# 24v_reg_motor.net
KiCad netlist of a schematic drawn in EAGLE
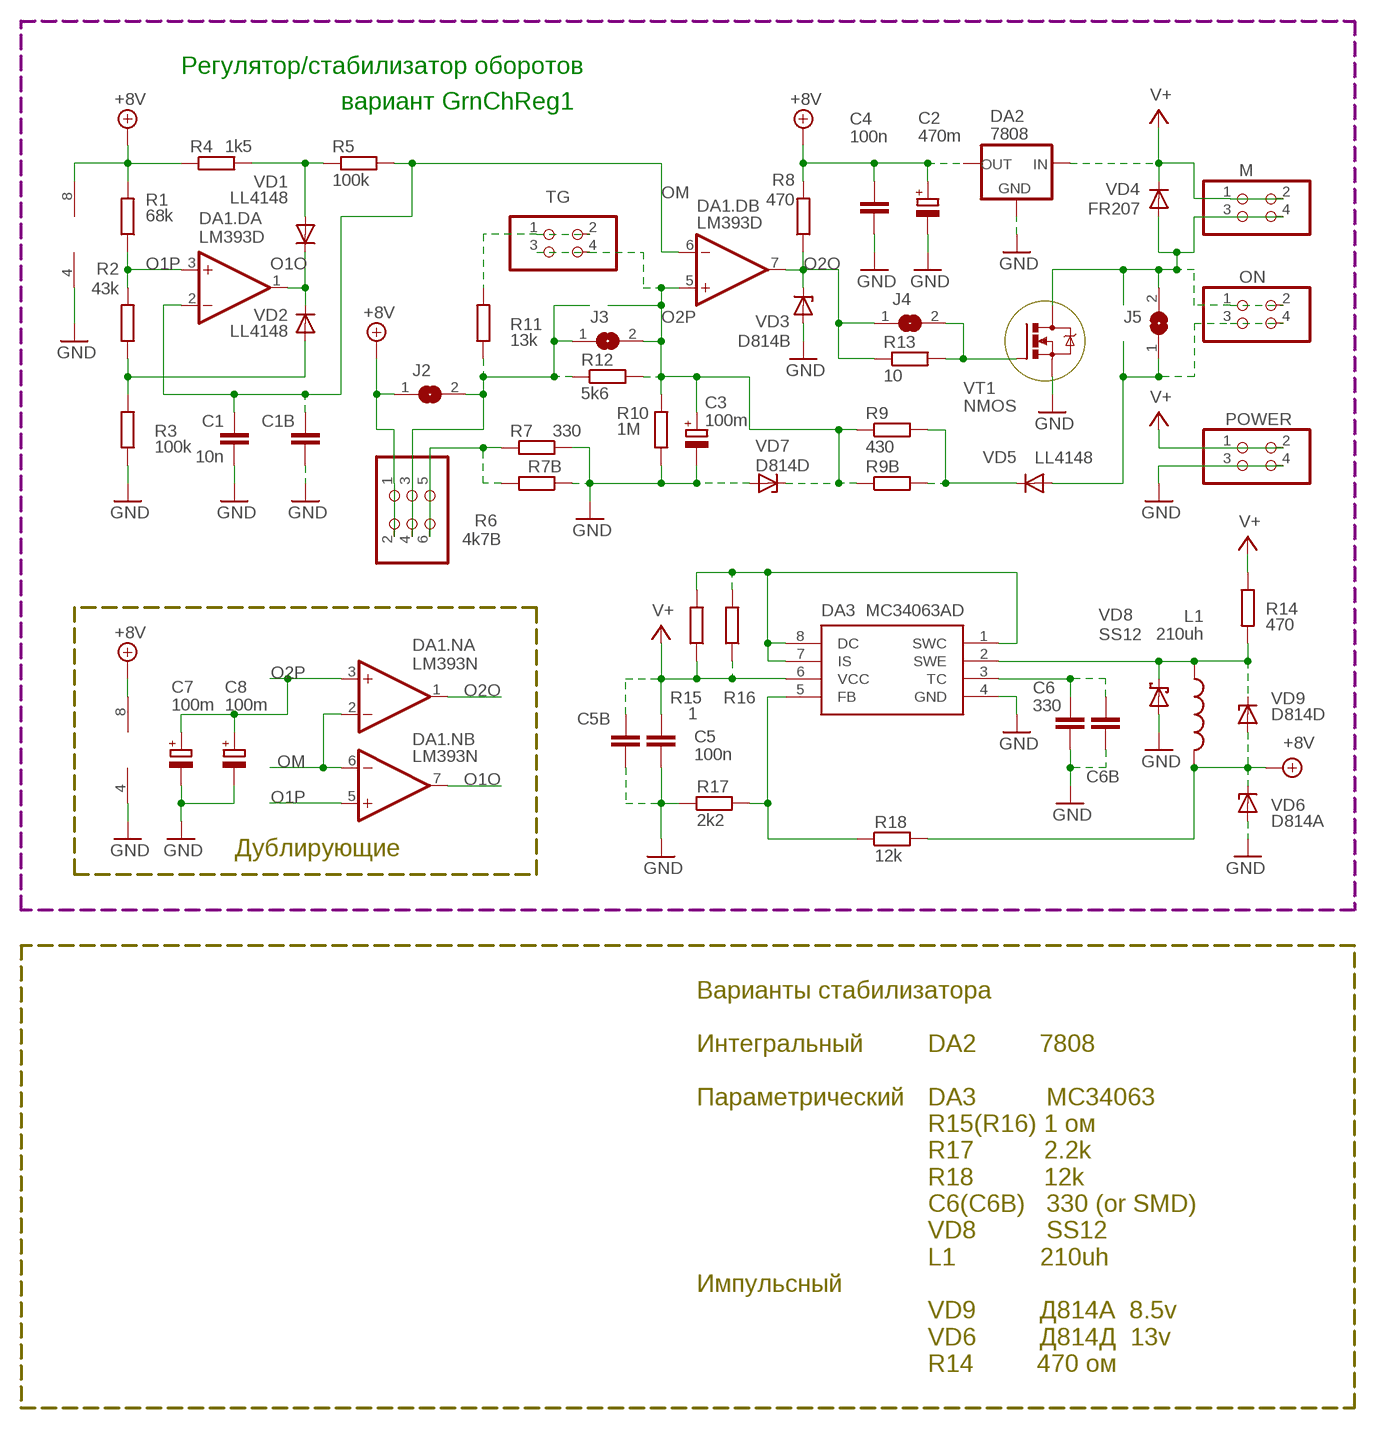
[diagram p0: schematic, sheet 1]

(export (version "E")
  (design (tool "Eeschema 10.0.6"))
  (components
    (comp (ref "C1")
      (value "10n")
      (footprint "eagle-import:C025-025X050")
      (libsource (lib "eagle-import") (part "rcl_C-EU025-025X050"))
    )
    (comp (ref "C1B")
      (value "C-EUC0805")
      (footprint "eagle-import:C0805")
      (libsource (lib "eagle-import") (part "rcl_C-EUC0805"))
    )
    (comp (ref "C2")
      (value "470m")
      (footprint "eagle-import:E5-8,5")
      (libsource (lib "eagle-import") (part "CPOL-EUE5-8.5"))
    )
    (comp (ref "C3")
      (value "100m")
      (footprint "eagle-import:E2,5-7")
      (libsource (lib "eagle-import") (part "CPOL-EUE2.5-7"))
    )
    (comp (ref "C4")
      (value "100n")
      (footprint "eagle-import:C1206K")
      (libsource (lib "eagle-import") (part "rcl_C-EUC1206K"))
    )
    (comp (ref "C5")
      (value "100n")
      (footprint "eagle-import:C025-024X044")
      (libsource (lib "eagle-import") (part "C-EU025-024X044"))
    )
    (comp (ref "C5B")
      (value "C-EUC1206")
      (footprint "eagle-import:C1206")
      (libsource (lib "eagle-import") (part "C-EUC1206"))
    )
    (comp (ref "C6")
      (value "330")
      (footprint "eagle-import:C025-025X050")
      (libsource (lib "eagle-import") (part "rcl_C-EU025-025X050"))
    )
    (comp (ref "C6B")
      (value "C-EUC0805")
      (footprint "eagle-import:C0805")
      (libsource (lib "eagle-import") (part "rcl_C-EUC0805"))
    )
    (comp (ref "C7")
      (value "100m")
      (footprint "eagle-import:E22-6")
      (libsource (lib "eagle-import") (part "CPOL-EUE22-6AXIAL"))
    )
    (comp (ref "C8")
      (value "100m")
      (footprint "eagle-import:E22-6")
      (libsource (lib "eagle-import") (part "CPOL-EUE22-6AXIAL"))
    )
    (comp (ref "DA1.D")
      (value "LM393D")
      (footprint "eagle-import:SO08")
      (libsource (lib "eagle-import") (part "LM393D"))
    )
    (comp (ref "DA1.N")
      (value "LM393N")
      (footprint "eagle-import:DIL08")
      (libsource (lib "eagle-import") (part "LM393N"))
    )
    (comp (ref "DA2")
      (value "7808")
      (footprint "eagle-import:79XXL")
      (libsource (lib "eagle-import") (part "79XXL"))
    )
    (comp (ref "DA3")
      (value "MC34063AD")
      (footprint "eagle-import:SOIC8")
      (libsource (lib "eagle-import") (part "MC34063AD"))
    )
    (comp (ref "J2") (value "SJ") (footprint "eagle-import:SJ") (libsource (lib "eagle-import") (part "SJ")))
    (comp (ref "J3") (value "SJ") (footprint "eagle-import:SJ") (libsource (lib "eagle-import") (part "SJ")))
    (comp (ref "J4") (value "SJ") (footprint "eagle-import:SJ") (libsource (lib "eagle-import") (part "SJ")))
    (comp (ref "J5") (value "SJ") (footprint "eagle-import:SJ") (libsource (lib "eagle-import") (part "SJ")))
    (comp (ref "L1")
      (value "210uh")
      (footprint "eagle-import:0207_10")
      (libsource (lib "eagle-import") (part "L-US0207/10"))
    )
    (comp (ref "M")
      (value "PINHD-2X2")
      (footprint "eagle-import:2X02")
      (libsource (lib "eagle-import") (part "PINHD-2X2"))
    )
    (comp (ref "ON")
      (value "PINHD-2X2")
      (footprint "eagle-import:2X02")
      (libsource (lib "eagle-import") (part "PINHD-2X2"))
    )
    (comp (ref "POWER")
      (value "PINHD-2X2")
      (footprint "eagle-import:2X02")
      (libsource (lib "eagle-import") (part "PINHD-2X2"))
    )
    (comp (ref "R1")
      (value "68k")
      (footprint "eagle-import:0207_10")
      (libsource (lib "eagle-import") (part "R-EU_0207/10"))
    )
    (comp (ref "R2")
      (value "43k")
      (footprint "eagle-import:M0805")
      (libsource (lib "eagle-import") (part "R-EU_M0805"))
    )
    (comp (ref "R3")
      (value "100k")
      (footprint "eagle-import:M0805")
      (libsource (lib "eagle-import") (part "R-EU_M0805"))
    )
    (comp (ref "R4")
      (value "1k5")
      (footprint "eagle-import:M0805")
      (libsource (lib "eagle-import") (part "R-EU_M0805"))
    )
    (comp (ref "R5")
      (value "100k")
      (footprint "eagle-import:M0805")
      (libsource (lib "eagle-import") (part "R-EU_M0805"))
    )
    (comp (ref "R6")
      (value "4k7B")
      (footprint "eagle-import:2X03")
      (libsource (lib "eagle-import") (part "PINHD-2X3"))
    )
    (comp (ref "R7")
      (value "330")
      (footprint "eagle-import:0309_10")
      (libsource (lib "eagle-import") (part "R-EU_0309/10"))
    )
    (comp (ref "R7B")
      (value "R-EU_M0805")
      (footprint "eagle-import:M0805")
      (libsource (lib "eagle-import") (part "R-EU_M0805"))
    )
    (comp (ref "R8")
      (value "470")
      (footprint "eagle-import:M0805")
      (libsource (lib "eagle-import") (part "R-EU_M0805"))
    )
    (comp (ref "R9")
      (value "430")
      (footprint "eagle-import:0207_10")
      (libsource (lib "eagle-import") (part "R-EU_0207/10"))
    )
    (comp (ref "R9B")
      (value "R-EU_R0805")
      (footprint "eagle-import:R0805")
      (libsource (lib "eagle-import") (part "R-EU_R0805"))
    )
    (comp (ref "R10")
      (value "1M")
      (footprint "eagle-import:M0805")
      (libsource (lib "eagle-import") (part "R-EU_M0805"))
    )
    (comp (ref "R11")
      (value "13k")
      (footprint "eagle-import:0207_10")
      (libsource (lib "eagle-import") (part "R-EU_0207/10"))
    )
    (comp (ref "R12")
      (value "5k6")
      (footprint "eagle-import:M0805")
      (libsource (lib "eagle-import") (part "R-EU_M0805"))
    )
    (comp (ref "R13")
      (value "10")
      (footprint "eagle-import:R0805")
      (libsource (lib "eagle-import") (part "R-EU_R0805"))
    )
    (comp (ref "R14")
      (value "470")
      (footprint "eagle-import:0207_10")
      (libsource (lib "eagle-import") (part "R-EU_0207/10"))
    )
    (comp (ref "R15")
      (value "1")
      (footprint "eagle-import:M0805")
      (libsource (lib "eagle-import") (part "R-EU_M0805"))
    )
    (comp (ref "R16")
      (value "R-EU_M0805")
      (footprint "eagle-import:M0805")
      (libsource (lib "eagle-import") (part "R-EU_M0805"))
    )
    (comp (ref "R17")
      (value "2k2")
      (footprint "eagle-import:M0805")
      (libsource (lib "eagle-import") (part "R-EU_M0805"))
    )
    (comp (ref "R18")
      (value "12k")
      (footprint "eagle-import:0207_10")
      (libsource (lib "eagle-import") (part "R-EU_0207/10"))
    )
    (comp (ref "TG")
      (value "PINHD-2X2")
      (footprint "eagle-import:2X02")
      (libsource (lib "eagle-import") (part "PINHD-2X2"))
    )
    (comp (ref "VD1")
      (value "LL4148")
      (footprint "eagle-import:SOD80C")
      (libsource (lib "eagle-import") (part "DIODE-SOD80C"))
    )
    (comp (ref "VD2")
      (value "LL4148")
      (footprint "eagle-import:SOD80C")
      (libsource (lib "eagle-import") (part "DIODE-SOD80C"))
    )
    (comp (ref "VD3")
      (value "D814B")
      (footprint "eagle-import:ZDMETAL")
      (libsource (lib "eagle-import") (part "ZDD814"))
    )
    (comp (ref "VD4")
      (value "FR207")
      (footprint "eagle-import:DO35-10")
      (libsource (lib "eagle-import") (part "1N4148DO35-10"))
    )
    (comp (ref "VD5")
      (value "LL4148")
      (footprint "eagle-import:SOD80C")
      (libsource (lib "eagle-import") (part "DIODE-SOD80C"))
    )
    (comp (ref "VD6")
      (value "D814A")
      (footprint "eagle-import:ZDMETAL")
      (libsource (lib "eagle-import") (part "ZDD814"))
    )
    (comp (ref "VD7")
      (value "D814D")
      (footprint "eagle-import:ZDMETAL")
      (libsource (lib "eagle-import") (part "ZDD814"))
    )
    (comp (ref "VD8")
      (value "SS12")
      (footprint "eagle-import:SMB")
      (libsource (lib "eagle-import") (part "SCHOTTKY-DIODESMD"))
    )
    (comp (ref "VD9")
      (value "D814D")
      (footprint "eagle-import:ZDMETAL")
      (libsource (lib "eagle-import") (part "ZDD814"))
    )
    (comp (ref "VT1")
      (value "NMOS")
      (footprint "eagle-import:DPACK_1")
      (libsource (lib "eagle-import") (part "NMOSD"))
    )
  )
  (nets
    (net (code "1") (name "+8V") (class "Default")
      (node (ref "C2") (pin "+") (pinfunction "+_+") (pintype "passive"))
      (node (ref "C4") (pin "1") (pinfunction "1_1") (pintype "passive"))
      (node (ref "DA1.D") (pin "8") (pinfunction "V+_8") (pintype "power_in"))
      (node (ref "DA1.N") (pin "8") (pinfunction "V+_8") (pintype "power_in"))
      (node (ref "DA2") (pin "OUT") (pinfunction "OUT_OUT") (pintype "passive"))
      (node (ref "J2") (pin "1") (pinfunction "1_1") (pintype "passive"))
      (node (ref "L1") (pin "2") (pinfunction "2_2") (pintype "passive"))
      (node (ref "R1") (pin "2") (pinfunction "2_2") (pintype "passive"))
      (node (ref "R18") (pin "2") (pinfunction "2_2") (pintype "passive"))
      (node (ref "R4") (pin "1") (pinfunction "1_1") (pintype "passive"))
      (node (ref "R6") (pin "1") (pinfunction "1_1") (pintype "passive"))
      (node (ref "R6") (pin "2") (pinfunction "2_2") (pintype "passive"))
      (node (ref "R8") (pin "2") (pinfunction "2_2") (pintype "passive"))
      (node (ref "VD6") (pin "C") (pinfunction "C_C") (pintype "passive"))
      (node (ref "VD9") (pin "A") (pinfunction "A_A") (pintype "passive"))
    )
    (net (code "2") (name "/O1O") (class "Default")
      (node (ref "DA1.D") (pin "1") (pinfunction "OUT_1") (pintype "output"))
      (node (ref "DA1.N") (pin "7") (pinfunction "OUT_7") (pintype "output"))
      (node (ref "VD1") (pin "C") (pinfunction "C_C") (pintype "passive"))
      (node (ref "VD2") (pin "C") (pinfunction "C_C") (pintype "passive"))
    )
    (net (code "3") (name "/O1P") (class "Default")
      (node (ref "DA1.D") (pin "3") (pinfunction "+IN_3") (pintype "input"))
      (node (ref "DA1.N") (pin "5") (pinfunction "+IN_5") (pintype "input"))
      (node (ref "R1") (pin "1") (pinfunction "1_1") (pintype "passive"))
      (node (ref "R2") (pin "2") (pinfunction "2_2") (pintype "passive"))
    )
    (net (code "4") (name "/O2O") (class "Default")
      (node (ref "DA1.D") (pin "7") (pinfunction "OUT_7") (pintype "output"))
      (node (ref "DA1.N") (pin "1") (pinfunction "OUT_1") (pintype "output"))
      (node (ref "J4") (pin "1") (pinfunction "1_1") (pintype "passive"))
      (node (ref "R13") (pin "1") (pinfunction "1_1") (pintype "passive"))
      (node (ref "R8") (pin "1") (pinfunction "1_1") (pintype "passive"))
      (node (ref "VD3") (pin "C") (pinfunction "C_C") (pintype "passive"))
    )
    (net (code "5") (name "/O2P") (class "Default")
      (node (ref "C3") (pin "+") (pinfunction "+_+") (pintype "passive"))
      (node (ref "C7") (pin "+") (pinfunction "+_+") (pintype "passive"))
      (node (ref "C8") (pin "+") (pinfunction "+_+") (pintype "passive"))
      (node (ref "DA1.D") (pin "5") (pinfunction "+IN_5") (pintype "input"))
      (node (ref "DA1.N") (pin "3") (pinfunction "+IN_3") (pintype "input"))
      (node (ref "J3") (pin "2") (pinfunction "2_2") (pintype "passive"))
      (node (ref "R10") (pin "2") (pinfunction "2_2") (pintype "passive"))
      (node (ref "R12") (pin "2") (pinfunction "2_2") (pintype "passive"))
      (node (ref "R9") (pin "1") (pinfunction "1_1") (pintype "passive"))
      (node (ref "R9B") (pin "1") (pinfunction "1_1") (pintype "passive"))
      (node (ref "TG") (pin "3") (pinfunction "3_3") (pintype "passive"))
      (node (ref "TG") (pin "4") (pinfunction "4_4") (pintype "passive"))
      (node (ref "VD7") (pin "C") (pinfunction "C_C") (pintype "passive"))
    )
    (net (code "6") (name "/OM") (class "Default")
      (node (ref "C1") (pin "1") (pinfunction "1_1") (pintype "passive"))
      (node (ref "C1B") (pin "1") (pinfunction "1_1") (pintype "passive"))
      (node (ref "DA1.D") (pin "2") (pinfunction "-IN_2") (pintype "input"))
      (node (ref "DA1.D") (pin "6") (pinfunction "-IN_6") (pintype "input"))
      (node (ref "DA1.N") (pin "2") (pinfunction "-IN_2") (pintype "input"))
      (node (ref "DA1.N") (pin "6") (pinfunction "-IN_6") (pintype "input"))
      (node (ref "R5") (pin "2") (pinfunction "2_2") (pintype "passive"))
    )
    (net (code "7") (name "GND") (class "Default")
      (node (ref "C1") (pin "2") (pinfunction "2_2") (pintype "passive"))
      (node (ref "C1B") (pin "2") (pinfunction "2_2") (pintype "passive"))
      (node (ref "C2") (pin "-") (pinfunction "-_-") (pintype "passive"))
      (node (ref "C3") (pin "-") (pinfunction "-_-") (pintype "passive"))
      (node (ref "C4") (pin "2") (pinfunction "2_2") (pintype "passive"))
      (node (ref "C5") (pin "2") (pinfunction "2_2") (pintype "passive"))
      (node (ref "C5B") (pin "2") (pinfunction "2_2") (pintype "passive"))
      (node (ref "C6") (pin "2") (pinfunction "2_2") (pintype "passive"))
      (node (ref "C6B") (pin "2") (pinfunction "2_2") (pintype "passive"))
      (node (ref "C7") (pin "-") (pinfunction "-_-") (pintype "passive"))
      (node (ref "C8") (pin "-") (pinfunction "-_-") (pintype "passive"))
      (node (ref "DA1.D") (pin "4") (pinfunction "V-_4") (pintype "power_in"))
      (node (ref "DA1.N") (pin "4") (pinfunction "V-_4") (pintype "power_in"))
      (node (ref "DA2") (pin "GND") (pinfunction "GND_GND") (pintype "input"))
      (node (ref "DA3") (pin "4") (pinfunction "GND_4") (pintype "passive"))
      (node (ref "POWER") (pin "3") (pinfunction "3_3") (pintype "passive"))
      (node (ref "POWER") (pin "4") (pinfunction "4_4") (pintype "passive"))
      (node (ref "R10") (pin "1") (pinfunction "1_1") (pintype "passive"))
      (node (ref "R17") (pin "1") (pinfunction "1_1") (pintype "passive"))
      (node (ref "R3") (pin "1") (pinfunction "1_1") (pintype "passive"))
      (node (ref "R7") (pin "1") (pinfunction "1_1") (pintype "passive"))
      (node (ref "R7B") (pin "1") (pinfunction "1_1") (pintype "passive"))
      (node (ref "VD3") (pin "A") (pinfunction "A_A") (pintype "passive"))
      (node (ref "VD6") (pin "A") (pinfunction "A_A") (pintype "passive"))
      (node (ref "VD7") (pin "A") (pinfunction "A_A") (pintype "passive"))
      (node (ref "VD8") (pin "A") (pinfunction "A_A") (pintype "passive"))
      (node (ref "VT1") (pin "S") (pinfunction "S_S") (pintype "passive"))
    )
    (net (code "8") (name "Net-(DA3-DC)") (class "Default")
      (node (ref "DA3") (pin "1") (pinfunction "SWC_1") (pintype "passive"))
      (node (ref "DA3") (pin "7") (pinfunction "IS_7") (pintype "passive"))
      (node (ref "DA3") (pin "8") (pinfunction "DC_8") (pintype "passive"))
      (node (ref "R15") (pin "2") (pinfunction "2_2") (pintype "passive"))
      (node (ref "R16") (pin "2") (pinfunction "2_2") (pintype "passive"))
    )
    (net (code "9") (name "Net-(DA3-FB)") (class "Default")
      (node (ref "DA3") (pin "5") (pinfunction "FB_5") (pintype "passive"))
      (node (ref "R17") (pin "2") (pinfunction "2_2") (pintype "passive"))
      (node (ref "R18") (pin "1") (pinfunction "1_1") (pintype "passive"))
    )
    (net (code "10") (name "Net-(DA3-SWE)") (class "Default")
      (node (ref "DA3") (pin "2") (pinfunction "SWE_2") (pintype "passive"))
      (node (ref "L1") (pin "1") (pinfunction "1_1") (pintype "passive"))
      (node (ref "R14") (pin "2") (pinfunction "2_2") (pintype "passive"))
      (node (ref "VD8") (pin "C") (pinfunction "C_C") (pintype "passive"))
      (node (ref "VD9") (pin "C") (pinfunction "C_C") (pintype "passive"))
    )
    (net (code "11") (name "Net-(DA3-TC)") (class "Default")
      (node (ref "C6") (pin "1") (pinfunction "1_1") (pintype "passive"))
      (node (ref "C6B") (pin "1") (pinfunction "1_1") (pintype "passive"))
      (node (ref "DA3") (pin "3") (pinfunction "TC_3") (pintype "passive"))
    )
    (net (code "12") (name "Net-(J2-Pad2)") (class "Default")
      (node (ref "J2") (pin "2") (pinfunction "2_2") (pintype "passive"))
      (node (ref "J3") (pin "1") (pinfunction "1_1") (pintype "passive"))
      (node (ref "R11") (pin "1") (pinfunction "1_1") (pintype "passive"))
      (node (ref "R12") (pin "1") (pinfunction "1_1") (pintype "passive"))
      (node (ref "R6") (pin "3") (pinfunction "3_3") (pintype "passive"))
      (node (ref "R6") (pin "4") (pinfunction "4_4") (pintype "passive"))
    )
    (net (code "13") (name "Net-(J4-Pad2)") (class "Default")
      (node (ref "J4") (pin "2") (pinfunction "2_2") (pintype "passive"))
      (node (ref "R13") (pin "2") (pinfunction "2_2") (pintype "passive"))
      (node (ref "VT1") (pin "G") (pinfunction "G_G") (pintype "passive"))
    )
    (net (code "14") (name "Net-(J5-Pad1)") (class "Default")
      (node (ref "J5") (pin "1") (pinfunction "1_1") (pintype "passive"))
      (node (ref "ON") (pin "3") (pinfunction "3_3") (pintype "passive"))
      (node (ref "ON") (pin "4") (pinfunction "4_4") (pintype "passive"))
      (node (ref "VD5") (pin "A") (pinfunction "A_A") (pintype "passive"))
    )
    (net (code "15") (name "Net-(J5-Pad2)") (class "Default")
      (node (ref "J5") (pin "2") (pinfunction "2_2") (pintype "passive"))
      (node (ref "M") (pin "3") (pinfunction "3_3") (pintype "passive"))
      (node (ref "M") (pin "4") (pinfunction "4_4") (pintype "passive"))
      (node (ref "ON") (pin "1") (pinfunction "1_1") (pintype "passive"))
      (node (ref "ON") (pin "2") (pinfunction "2_2") (pintype "passive"))
      (node (ref "VD4") (pin "A") (pinfunction "A_A") (pintype "passive"))
      (node (ref "VT1") (pin "D") (pinfunction "D_D") (pintype "passive"))
    )
    (net (code "16") (name "Net-(R2-Pad1)") (class "Default")
      (node (ref "R2") (pin "1") (pinfunction "1_1") (pintype "passive"))
      (node (ref "R3") (pin "2") (pinfunction "2_2") (pintype "passive"))
      (node (ref "VD2") (pin "A") (pinfunction "A_A") (pintype "passive"))
    )
    (net (code "17") (name "Net-(R4-Pad2)") (class "Default")
      (node (ref "R4") (pin "2") (pinfunction "2_2") (pintype "passive"))
      (node (ref "R5") (pin "1") (pinfunction "1_1") (pintype "passive"))
      (node (ref "VD1") (pin "A") (pinfunction "A_A") (pintype "passive"))
    )
    (net (code "18") (name "Net-(R6-Pad5)") (class "Default")
      (node (ref "R6") (pin "5") (pinfunction "5_5") (pintype "passive"))
      (node (ref "R6") (pin "6") (pinfunction "6_6") (pintype "passive"))
      (node (ref "R7") (pin "2") (pinfunction "2_2") (pintype "passive"))
      (node (ref "R7B") (pin "2") (pinfunction "2_2") (pintype "passive"))
    )
    (net (code "19") (name "Net-(R9-Pad2)") (class "Default")
      (node (ref "R9") (pin "2") (pinfunction "2_2") (pintype "passive"))
      (node (ref "R9B") (pin "2") (pinfunction "2_2") (pintype "passive"))
      (node (ref "VD5") (pin "C") (pinfunction "C_C") (pintype "passive"))
    )
    (net (code "20") (name "Net-(R11-Pad2)") (class "Default")
      (node (ref "R11") (pin "2") (pinfunction "2_2") (pintype "passive"))
      (node (ref "TG") (pin "1") (pinfunction "1_1") (pintype "passive"))
      (node (ref "TG") (pin "2") (pinfunction "2_2") (pintype "passive"))
    )
    (net (code "21") (name "V+") (class "Default")
      (node (ref "C5") (pin "1") (pinfunction "1_1") (pintype "passive"))
      (node (ref "C5B") (pin "1") (pinfunction "1_1") (pintype "passive"))
      (node (ref "DA2") (pin "IN") (pinfunction "IN_IN") (pintype "input"))
      (node (ref "DA3") (pin "6") (pinfunction "VCC_6") (pintype "passive"))
      (node (ref "M") (pin "1") (pinfunction "1_1") (pintype "passive"))
      (node (ref "M") (pin "2") (pinfunction "2_2") (pintype "passive"))
      (node (ref "POWER") (pin "1") (pinfunction "1_1") (pintype "passive"))
      (node (ref "POWER") (pin "2") (pinfunction "2_2") (pintype "passive"))
      (node (ref "R14") (pin "1") (pinfunction "1_1") (pintype "passive"))
      (node (ref "R15") (pin "1") (pinfunction "1_1") (pintype "passive"))
      (node (ref "R16") (pin "1") (pinfunction "1_1") (pintype "passive"))
      (node (ref "VD4") (pin "C") (pinfunction "C_C") (pintype "passive"))
    )
  )
)
